# Ver2_1.net
KiCad netlist of a schematic drawn in EAGLE
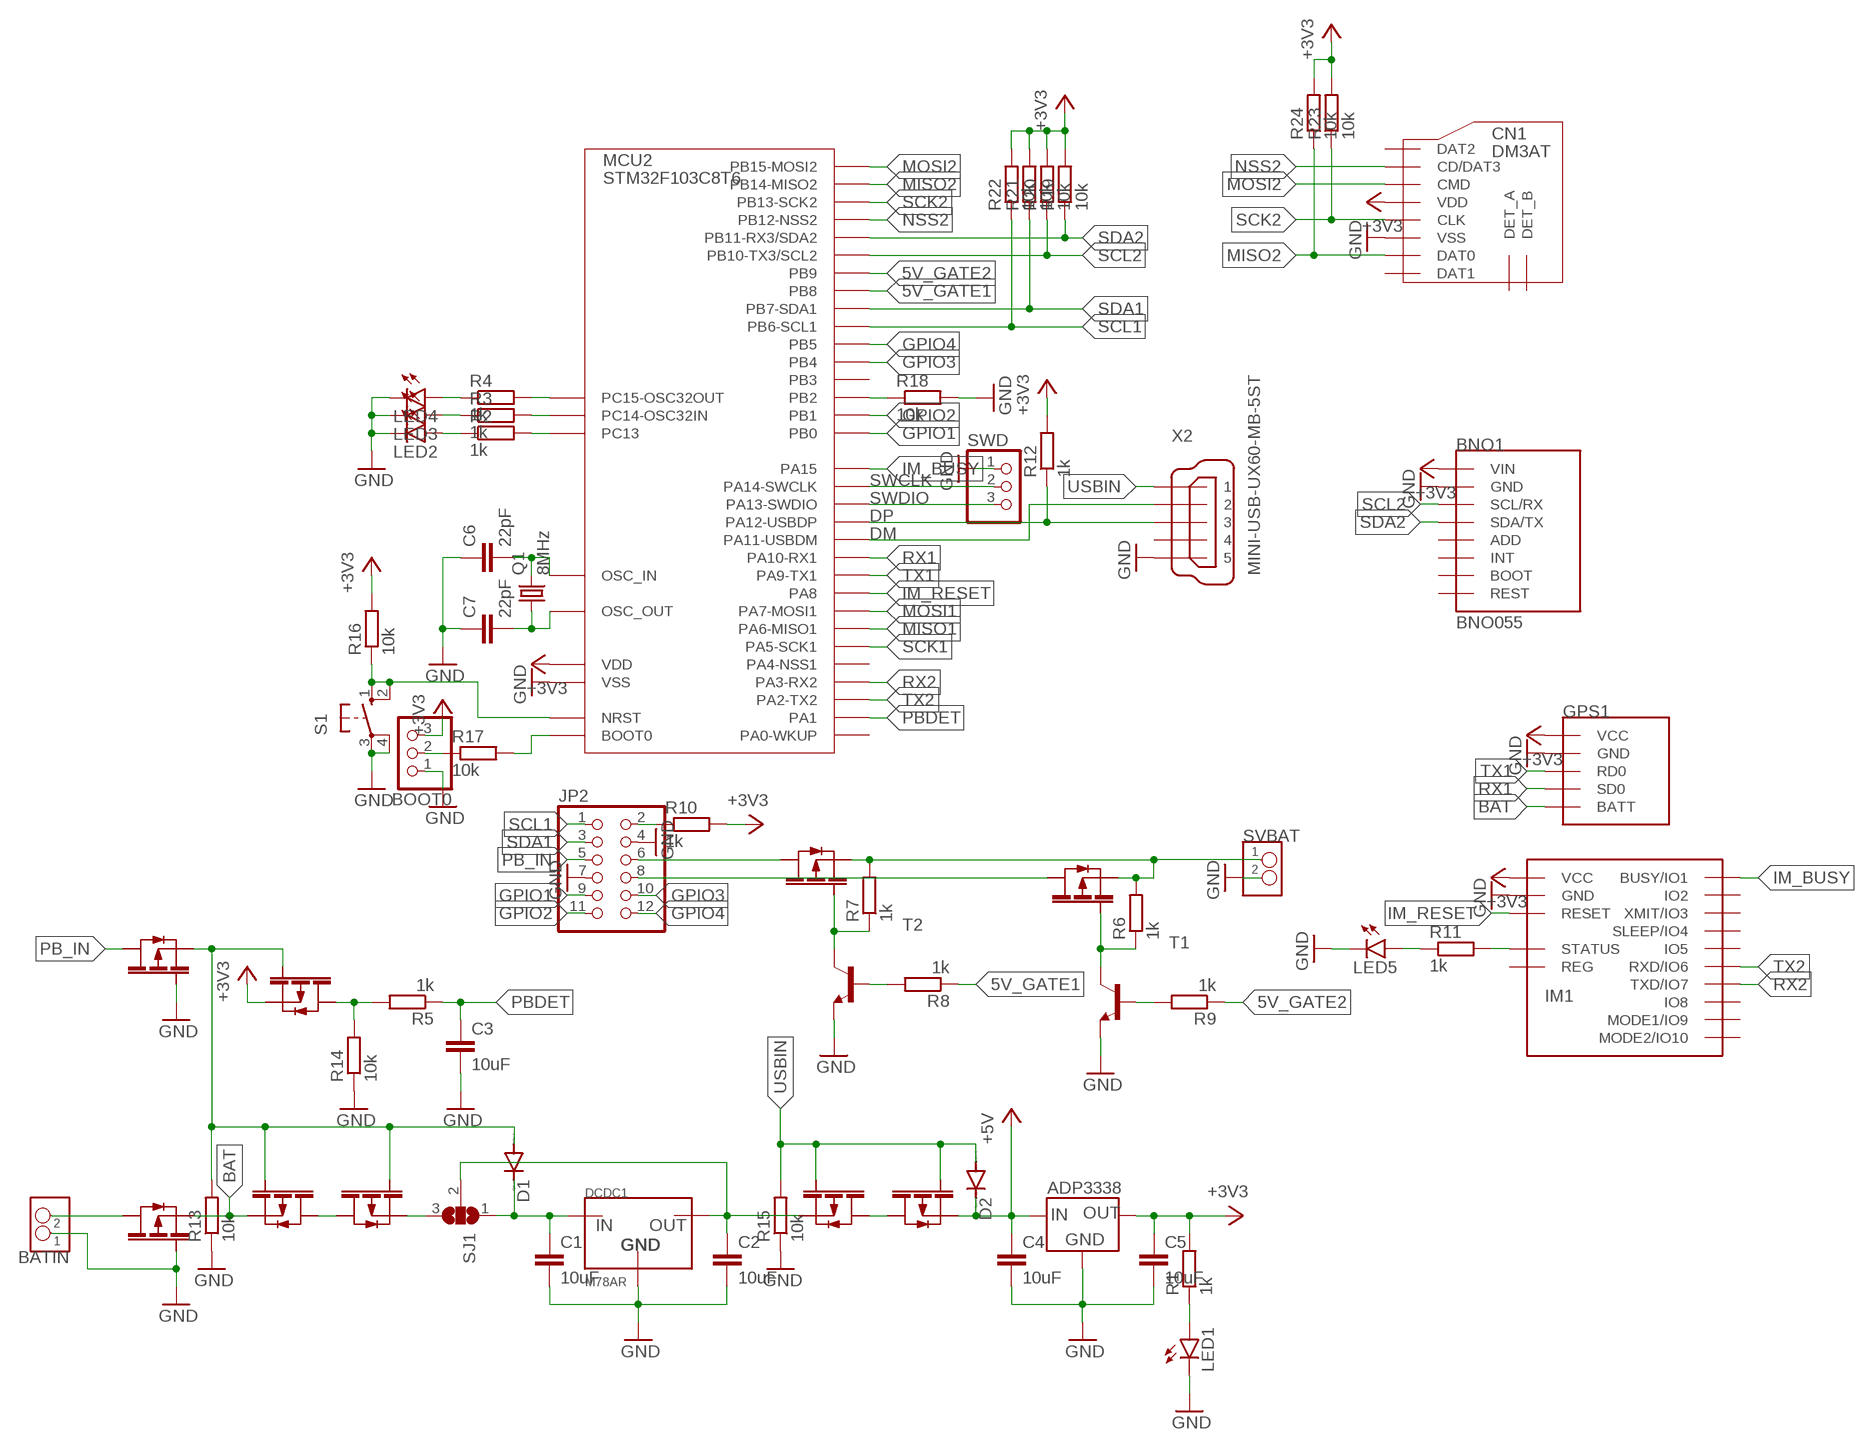
[diagram p0: schematic, sheet 1]

(export (version "E")
  (design (tool "Eeschema 10.0.6"))
  (components
    (comp (ref "BATIN")
      (value "S2B-XH-A")
      (footprint "eagle-import:S2B-XH-A")
      (libsource (lib "eagle-import") (part "S2B-XH-A"))
    )
    (comp (ref "BNO1")
      (value "BNO055")
      (footprint "eagle-import:BNO055")
      (libsource (lib "eagle-import") (part "BNO055"))
    )
    (comp (ref "BOOT0")
      (value "PINHD-1X3")
      (footprint "eagle-import:1X03")
      (libsource (lib "eagle-import") (part "PINHD-1X3"))
    )
    (comp (ref "C1")
      (value "10uF")
      (footprint "eagle-import:C2012")
      (libsource (lib "eagle-import") (part "C-EUC2012"))
    )
    (comp (ref "C2")
      (value "10uF")
      (footprint "eagle-import:C2012")
      (libsource (lib "eagle-import") (part "C-EUC2012"))
    )
    (comp (ref "C3")
      (value "10uF")
      (footprint "eagle-import:C2012")
      (libsource (lib "eagle-import") (part "C-EUC2012"))
    )
    (comp (ref "C4")
      (value "10uF")
      (footprint "eagle-import:C2012")
      (libsource (lib "eagle-import") (part "C-EUC2012"))
    )
    (comp (ref "C5")
      (value "10uF")
      (footprint "eagle-import:C2012")
      (libsource (lib "eagle-import") (part "C-EUC2012"))
    )
    (comp (ref "C6")
      (value "22pF")
      (footprint "eagle-import:C2012")
      (libsource (lib "eagle-import") (part "C-EUC2012"))
    )
    (comp (ref "C7")
      (value "22pF")
      (footprint "eagle-import:C2012")
      (libsource (lib "eagle-import") (part "C-EUC2012"))
    )
    (comp (ref "CN1")
      (value "DM3AT")
      (footprint "eagle-import:DM3AT")
      (libsource (lib "eagle-import") (part "DM3AT"))
    )
    (comp (ref "D1")
      (value "DIODE-SOD123")
      (footprint "eagle-import:SOD123")
      (libsource (lib "eagle-import") (part "DIODE-SOD123"))
    )
    (comp (ref "D2")
      (value "DIODE-SOD123")
      (footprint "eagle-import:SOD123")
      (libsource (lib "eagle-import") (part "DIODE-SOD123"))
    )
    (comp (ref "DCDC1")
      (value "M78AR")
      (footprint "eagle-import:M78AR")
      (libsource (lib "eagle-import") (part "M78AR"))
    )
    (comp (ref "FET1")
      (value "PCH")
      (footprint "eagle-import:SOT-23")
      (libsource (lib "eagle-import") (part "PCH"))
    )
    (comp (ref "FET2")
      (value "PCH")
      (footprint "eagle-import:SOT-23")
      (libsource (lib "eagle-import") (part "PCH"))
    )
    (comp (ref "FET3")
      (value "PCH")
      (footprint "eagle-import:SOT-23")
      (libsource (lib "eagle-import") (part "PCH"))
    )
    (comp (ref "FET4")
      (value "PCH")
      (footprint "eagle-import:SOT-23")
      (libsource (lib "eagle-import") (part "PCH"))
    )
    (comp (ref "FET5")
      (value "PCH")
      (footprint "eagle-import:SOT-23")
      (libsource (lib "eagle-import") (part "PCH"))
    )
    (comp (ref "FET6")
      (value "PCH")
      (footprint "eagle-import:SOT-23")
      (libsource (lib "eagle-import") (part "PCH"))
    )
    (comp (ref "FET7")
      (value "PCH")
      (footprint "eagle-import:SOT-23")
      (libsource (lib "eagle-import") (part "PCH"))
    )
    (comp (ref "FET8")
      (value "PCH")
      (footprint "eagle-import:SOT-23")
      (libsource (lib "eagle-import") (part "PCH"))
    )
    (comp (ref "FET9")
      (value "PCH")
      (footprint "eagle-import:SOT-23")
      (libsource (lib "eagle-import") (part "PCH"))
    )
    (comp (ref "GPS1")
      (value "GPS-54D")
      (footprint "eagle-import:GPS-54D")
      (libsource (lib "eagle-import") (part "GPS-54D"))
    )
    (comp (ref "IC1")
      (value "ADP3338-3.3")
      (footprint "eagle-import:SOT-223")
      (libsource (lib "eagle-import") (part "ADP3338-3.3"))
    )
    (comp (ref "IM1")
      (value "IM920C")
      (footprint "eagle-import:IM920C")
      (libsource (lib "eagle-import") (part "IM920C"))
    )
    (comp (ref "JP2")
      (value "PINHD-2X6")
      (footprint "eagle-import:2X06")
      (libsource (lib "eagle-import") (part "PINHD-2X6"))
    )
    (comp (ref "LED1")
      (value "LEDSMT1206")
      (footprint "eagle-import:1206")
      (libsource (lib "eagle-import") (part "LEDSMT1206"))
    )
    (comp (ref "LED2")
      (value "LEDSMT1206")
      (footprint "eagle-import:1206")
      (libsource (lib "eagle-import") (part "LEDSMT1206"))
    )
    (comp (ref "LED3")
      (value "LEDSMT1206")
      (footprint "eagle-import:1206")
      (libsource (lib "eagle-import") (part "LEDSMT1206"))
    )
    (comp (ref "LED4")
      (value "LEDSMT1206")
      (footprint "eagle-import:1206")
      (libsource (lib "eagle-import") (part "LEDSMT1206"))
    )
    (comp (ref "LED5")
      (value "LEDSMT1206")
      (footprint "eagle-import:1206")
      (libsource (lib "eagle-import") (part "LEDSMT1206"))
    )
    (comp (ref "MCU2")
      (value "STM32F103C8T6")
      (footprint "eagle-import:LQFP48")
      (libsource (lib "eagle-import") (part "STM32F103C8T6"))
    )
    (comp (ref "Q1")
      (value "8MHz")
      (footprint "eagle-import:HC49_S")
      (libsource (lib "eagle-import") (part "CRYSTALHC49S"))
    )
    (comp (ref "R1")
      (value "1k")
      (footprint "eagle-import:R2012")
      (libsource (lib "eagle-import") (part "R-EU_R2012"))
    )
    (comp (ref "R2")
      (value "1k")
      (footprint "eagle-import:R2012")
      (libsource (lib "eagle-import") (part "R-EU_R2012"))
    )
    (comp (ref "R3")
      (value "1k")
      (footprint "eagle-import:R2012")
      (libsource (lib "eagle-import") (part "R-EU_R2012"))
    )
    (comp (ref "R4")
      (value "1k")
      (footprint "eagle-import:R2012")
      (libsource (lib "eagle-import") (part "R-EU_R2012"))
    )
    (comp (ref "R5")
      (value "1k")
      (footprint "eagle-import:R2012")
      (libsource (lib "eagle-import") (part "R-EU_R2012"))
    )
    (comp (ref "R6")
      (value "1k")
      (footprint "eagle-import:R2012")
      (libsource (lib "eagle-import") (part "R-EU_R2012"))
    )
    (comp (ref "R7")
      (value "1k")
      (footprint "eagle-import:R2012")
      (libsource (lib "eagle-import") (part "R-EU_R2012"))
    )
    (comp (ref "R8")
      (value "1k")
      (footprint "eagle-import:R2012")
      (libsource (lib "eagle-import") (part "R-EU_R2012"))
    )
    (comp (ref "R9")
      (value "1k")
      (footprint "eagle-import:R2012")
      (libsource (lib "eagle-import") (part "R-EU_R2012"))
    )
    (comp (ref "R10")
      (value "1k")
      (footprint "eagle-import:R2012")
      (libsource (lib "eagle-import") (part "R-EU_R2012"))
    )
    (comp (ref "R11")
      (value "1k")
      (footprint "eagle-import:R2012")
      (libsource (lib "eagle-import") (part "R-EU_R2012"))
    )
    (comp (ref "R12")
      (value "1k")
      (footprint "eagle-import:R2012")
      (libsource (lib "eagle-import") (part "R-EU_R2012"))
    )
    (comp (ref "R13")
      (value "10k")
      (footprint "eagle-import:R2012")
      (libsource (lib "eagle-import") (part "R-EU_R2012"))
    )
    (comp (ref "R14")
      (value "10k")
      (footprint "eagle-import:R2012")
      (libsource (lib "eagle-import") (part "R-EU_R2012"))
    )
    (comp (ref "R15")
      (value "10k")
      (footprint "eagle-import:R2012")
      (libsource (lib "eagle-import") (part "R-EU_R2012"))
    )
    (comp (ref "R16")
      (value "10k")
      (footprint "eagle-import:R2012")
      (libsource (lib "eagle-import") (part "R-EU_R2012"))
    )
    (comp (ref "R17")
      (value "10k")
      (footprint "eagle-import:R2012")
      (libsource (lib "eagle-import") (part "R-EU_R2012"))
    )
    (comp (ref "R18")
      (value "10k")
      (footprint "eagle-import:R2012")
      (libsource (lib "eagle-import") (part "R-EU_R2012"))
    )
    (comp (ref "R19")
      (value "10k")
      (footprint "eagle-import:R2012")
      (libsource (lib "eagle-import") (part "R-EU_R2012"))
    )
    (comp (ref "R20")
      (value "10k")
      (footprint "eagle-import:R2012")
      (libsource (lib "eagle-import") (part "R-EU_R2012"))
    )
    (comp (ref "R21")
      (value "10k")
      (footprint "eagle-import:R2012")
      (libsource (lib "eagle-import") (part "R-EU_R2012"))
    )
    (comp (ref "R22")
      (value "10k")
      (footprint "eagle-import:R2012")
      (libsource (lib "eagle-import") (part "R-EU_R2012"))
    )
    (comp (ref "R23")
      (value "10k")
      (footprint "eagle-import:R2012")
      (libsource (lib "eagle-import") (part "R-EU_R2012"))
    )
    (comp (ref "R24")
      (value "10k")
      (footprint "eagle-import:R2012")
      (libsource (lib "eagle-import") (part "R-EU_R2012"))
    )
    (comp (ref "S1")
      (value "10-XX")
      (footprint "eagle-import:B3F-10XX")
      (fields (field (name "MPN") "B3F-1000"))
      (libsource (lib "eagle-import") (part "10-XX"))
    )
    (comp (ref "SJ1")
      (value "SJ2W")
      (footprint "eagle-import:SJ_2")
      (libsource (lib "eagle-import") (part "SJ2W"))
    )
    (comp (ref "SVBAT")
      (value "S2B-XH-A")
      (footprint "eagle-import:S2B-XH-A")
      (libsource (lib "eagle-import") (part "S2B-XH-A"))
    )
    (comp (ref "SWD")
      (value "PINHD-1X3")
      (footprint "eagle-import:1X03")
      (libsource (lib "eagle-import") (part "PINHD-1X3"))
    )
    (comp (ref "T1")
      (value "-NPN-SOT23-EBC")
      (footprint "eagle-import:SOT23-EBC")
      (libsource (lib "eagle-import") (part "-NPN-SOT23-EBC"))
    )
    (comp (ref "T2")
      (value "-NPN-SOT23-EBC")
      (footprint "eagle-import:SOT23-EBC")
      (libsource (lib "eagle-import") (part "-NPN-SOT23-EBC"))
    )
    (comp (ref "X2")
      (value "MINI-USB-UX60-MB-5ST")
      (footprint "eagle-import:UX60-MB-5ST")
      (libsource (lib "eagle-import") (part "MINI-USB-UX60-MB-5ST"))
    )
  )
  (nets
    (net (code "1") (name "+3V3") (class "Default")
      (node (ref "BNO1") (pin "P1") (pinfunction "VIN_P1") (pintype "bidirectional"))
      (node (ref "BOOT0") (pin "3") (pinfunction "3_3") (pintype "passive"))
      (node (ref "C5") (pin "1") (pinfunction "1_1") (pintype "passive"))
      (node (ref "CN1") (pin "VDD") (pinfunction "VDD_VDD") (pintype "bidirectional"))
      (node (ref "FET5") (pin "P$2") (pinfunction "P$2_P$2") (pintype "bidirectional"))
      (node (ref "GPS1") (pin "VCC") (pinfunction "VCC_VCC") (pintype "bidirectional"))
      (node (ref "IC1") (pin "1") (pinfunction "OUT_1") (pintype "output"))
      (node (ref "IC1") (pin "2") (pinfunction "OUT_2") (pintype "output"))
      (node (ref "IM1") (pin "$P17") (pinfunction "VCC_$P17") (pintype "bidirectional"))
      (node (ref "MCU2") (pin "1") (pinfunction "VDD_1") (pintype "bidirectional"))
      (node (ref "MCU2") (pin "24") (pinfunction "VDD_24") (pintype "bidirectional"))
      (node (ref "MCU2") (pin "36") (pinfunction "VDD_36") (pintype "bidirectional"))
      (node (ref "MCU2") (pin "48") (pinfunction "VDD_48") (pintype "bidirectional"))
      (node (ref "MCU2") (pin "9") (pinfunction "VDD_9") (pintype "bidirectional"))
      (node (ref "R1") (pin "2") (pinfunction "2_2") (pintype "passive"))
      (node (ref "R10") (pin "2") (pinfunction "2_2") (pintype "passive"))
      (node (ref "R12") (pin "2") (pinfunction "2_2") (pintype "passive"))
      (node (ref "R16") (pin "2") (pinfunction "2_2") (pintype "passive"))
      (node (ref "R19") (pin "2") (pinfunction "2_2") (pintype "passive"))
      (node (ref "R20") (pin "2") (pinfunction "2_2") (pintype "passive"))
      (node (ref "R21") (pin "2") (pinfunction "2_2") (pintype "passive"))
      (node (ref "R22") (pin "2") (pinfunction "2_2") (pintype "passive"))
      (node (ref "R23") (pin "2") (pinfunction "2_2") (pintype "passive"))
      (node (ref "R24") (pin "2") (pinfunction "2_2") (pintype "passive"))
    )
    (net (code "2") (name "+5V") (class "Default")
      (node (ref "C4") (pin "1") (pinfunction "1_1") (pintype "passive"))
      (node (ref "D2") (pin "C") (pinfunction "C_C") (pintype "passive"))
      (node (ref "FET7") (pin "P$2") (pinfunction "P$2_P$2") (pintype "bidirectional"))
      (node (ref "IC1") (pin "3") (pinfunction "IN_3") (pintype "input"))
    )
    (net (code "3") (name "/DM") (class "Default")
      (node (ref "MCU2") (pin "32") (pinfunction "PA11-USBDM_32") (pintype "bidirectional"))
      (node (ref "X2") (pin "2") (pinfunction "2_2") (pintype "input"))
    )
    (net (code "4") (name "/DP") (class "Default")
      (node (ref "MCU2") (pin "33") (pinfunction "PA12-USBDP_33") (pintype "bidirectional"))
      (node (ref "R12") (pin "1") (pinfunction "1_1") (pintype "passive"))
      (node (ref "X2") (pin "3") (pinfunction "3_3") (pintype "input"))
    )
    (net (code "5") (name "/SWCLK") (class "Default")
      (node (ref "MCU2") (pin "37") (pinfunction "PA14-SWCLK_37") (pintype "bidirectional"))
      (node (ref "SWD") (pin "2") (pinfunction "2_2") (pintype "passive"))
    )
    (net (code "6") (name "/SWDIO") (class "Default")
      (node (ref "MCU2") (pin "34") (pinfunction "PA13-SWDIO_34") (pintype "bidirectional"))
      (node (ref "SWD") (pin "3") (pinfunction "3_3") (pintype "passive"))
    )
    (net (code "7") (name "5V_GATE1") (class "Default")
      (node (ref "MCU2") (pin "45") (pinfunction "PB8_45") (pintype "bidirectional"))
      (node (ref "R8") (pin "1") (pinfunction "1_1") (pintype "passive"))
    )
    (net (code "8") (name "5V_GATE2") (class "Default")
      (node (ref "MCU2") (pin "46") (pinfunction "PB9_46") (pintype "bidirectional"))
      (node (ref "R9") (pin "1") (pinfunction "1_1") (pintype "passive"))
    )
    (net (code "9") (name "BAT") (class "Default")
      (node (ref "FET2") (pin "P$2") (pinfunction "P$2_P$2") (pintype "bidirectional"))
      (node (ref "FET3") (pin "P$2") (pinfunction "P$2_P$2") (pintype "bidirectional"))
      (node (ref "GPS1") (pin "BATT") (pinfunction "BATT_BATT") (pintype "bidirectional"))
    )
    (net (code "10") (name "GND") (class "Default")
      (node (ref "BATIN") (pin "P$1") (pinfunction "1_P$1") (pintype "bidirectional"))
      (node (ref "BNO1") (pin "P2") (pinfunction "GND_P2") (pintype "bidirectional"))
      (node (ref "BOOT0") (pin "1") (pinfunction "1_1") (pintype "passive"))
      (node (ref "C1") (pin "2") (pinfunction "2_2") (pintype "passive"))
      (node (ref "C2") (pin "2") (pinfunction "2_2") (pintype "passive"))
      (node (ref "C3") (pin "2") (pinfunction "2_2") (pintype "passive"))
      (node (ref "C4") (pin "2") (pinfunction "2_2") (pintype "passive"))
      (node (ref "C5") (pin "2") (pinfunction "2_2") (pintype "passive"))
      (node (ref "C6") (pin "1") (pinfunction "1_1") (pintype "passive"))
      (node (ref "C7") (pin "1") (pinfunction "1_1") (pintype "passive"))
      (node (ref "CN1") (pin "VSS") (pinfunction "VSS_VSS") (pintype "bidirectional"))
      (node (ref "DCDC1") (pin "P2") (pinfunction "GND_P2") (pintype "bidirectional"))
      (node (ref "FET1") (pin "P$1") (pinfunction "P$1_P$1") (pintype "bidirectional"))
      (node (ref "FET2") (pin "P$1") (pinfunction "P$1_P$1") (pintype "bidirectional"))
      (node (ref "GPS1") (pin "GND") (pinfunction "GND_GND") (pintype "bidirectional"))
      (node (ref "IC1") (pin "4") (pinfunction "GND_4") (pintype "bidirectional"))
      (node (ref "IM1") (pin "$P18") (pinfunction "GND_$P18") (pintype "bidirectional"))
      (node (ref "JP2") (pin "4") (pinfunction "4_4") (pintype "passive"))
      (node (ref "JP2") (pin "7") (pinfunction "7_7") (pintype "passive"))
      (node (ref "LED1") (pin "C") (pinfunction "C_C") (pintype "passive"))
      (node (ref "LED2") (pin "C") (pinfunction "C_C") (pintype "passive"))
      (node (ref "LED3") (pin "C") (pinfunction "C_C") (pintype "passive"))
      (node (ref "LED4") (pin "C") (pinfunction "C_C") (pintype "passive"))
      (node (ref "LED5") (pin "C") (pinfunction "C_C") (pintype "passive"))
      (node (ref "MCU2") (pin "23") (pinfunction "VSS_23") (pintype "bidirectional"))
      (node (ref "MCU2") (pin "35") (pinfunction "VSS_35") (pintype "bidirectional"))
      (node (ref "MCU2") (pin "47") (pinfunction "VSS_47") (pintype "bidirectional"))
      (node (ref "MCU2") (pin "8") (pinfunction "VSS_8") (pintype "bidirectional"))
      (node (ref "R13") (pin "1") (pinfunction "1_1") (pintype "passive"))
      (node (ref "R14") (pin "1") (pinfunction "1_1") (pintype "passive"))
      (node (ref "R15") (pin "1") (pinfunction "1_1") (pintype "passive"))
      (node (ref "R18") (pin "2") (pinfunction "2_2") (pintype "passive"))
      (node (ref "S1") (pin "3") (pinfunction "P_3") (pintype "passive"))
      (node (ref "S1") (pin "4") (pinfunction "P1_4") (pintype "passive"))
      (node (ref "SVBAT") (pin "P$2") (pinfunction "2_P$2") (pintype "bidirectional"))
      (node (ref "SWD") (pin "1") (pinfunction "1_1") (pintype "passive"))
      (node (ref "T1") (pin "E") (pinfunction "E_E") (pintype "passive"))
      (node (ref "T2") (pin "E") (pinfunction "E_E") (pintype "passive"))
      (node (ref "X2") (pin "5") (pinfunction "5_5") (pintype "input"))
    )
    (net (code "11") (name "GPIO1") (class "Default")
      (node (ref "JP2") (pin "9") (pinfunction "9_9") (pintype "passive"))
      (node (ref "MCU2") (pin "18") (pinfunction "PB0_18") (pintype "bidirectional"))
    )
    (net (code "12") (name "GPIO2") (class "Default")
      (node (ref "JP2") (pin "11") (pinfunction "11_11") (pintype "passive"))
      (node (ref "MCU2") (pin "19") (pinfunction "PB1_19") (pintype "bidirectional"))
    )
    (net (code "13") (name "GPIO3") (class "Default")
      (node (ref "JP2") (pin "10") (pinfunction "10_10") (pintype "passive"))
      (node (ref "MCU2") (pin "40") (pinfunction "PB4_40") (pintype "bidirectional"))
    )
    (net (code "14") (name "GPIO4") (class "Default")
      (node (ref "JP2") (pin "12") (pinfunction "12_12") (pintype "passive"))
      (node (ref "MCU2") (pin "41") (pinfunction "PB5_41") (pintype "bidirectional"))
    )
    (net (code "15") (name "IM_BUSY") (class "Default")
      (node (ref "IM1") (pin "$P1") (pinfunction "BUSY/IO1_$P1") (pintype "bidirectional"))
      (node (ref "MCU2") (pin "38") (pinfunction "PA15_38") (pintype "bidirectional"))
    )
    (net (code "16") (name "IM_RESET") (class "Default")
      (node (ref "IM1") (pin "$P19") (pinfunction "RESET_$P19") (pintype "bidirectional"))
      (node (ref "MCU2") (pin "29") (pinfunction "PA8_29") (pintype "bidirectional"))
    )
    (net (code "17") (name "MISO1") (class "Default")
      (node (ref "MCU2") (pin "16") (pinfunction "PA6-MISO1_16") (pintype "bidirectional"))
    )
    (net (code "18") (name "MISO2") (class "Default")
      (node (ref "CN1") (pin "DAT0") (pinfunction "DAT0_DAT0") (pintype "bidirectional"))
      (node (ref "MCU2") (pin "27") (pinfunction "PB14-MISO2_27") (pintype "bidirectional"))
      (node (ref "R24") (pin "1") (pinfunction "1_1") (pintype "passive"))
    )
    (net (code "19") (name "MOSI1") (class "Default")
      (node (ref "MCU2") (pin "17") (pinfunction "PA7-MOSI1_17") (pintype "bidirectional"))
    )
    (net (code "20") (name "MOSI2") (class "Default")
      (node (ref "CN1") (pin "CMD") (pinfunction "CMD_CMD") (pintype "bidirectional"))
      (node (ref "MCU2") (pin "28") (pinfunction "PB15-MOSI2_28") (pintype "bidirectional"))
    )
    (net (code "21") (name "NSS2") (class "Default")
      (node (ref "CN1") (pin "CD/DAT3") (pinfunction "CD/DAT3_CD/DAT3") (pintype "bidirectional"))
      (node (ref "MCU2") (pin "25") (pinfunction "PB12-NSS2_25") (pintype "bidirectional"))
    )
    (net (code "22") (name "Net-(BATIN-2)") (class "Default")
      (node (ref "BATIN") (pin "P$2") (pinfunction "2_P$2") (pintype "bidirectional"))
      (node (ref "FET2") (pin "P$3") (pinfunction "P$3_P$3") (pintype "bidirectional"))
    )
    (net (code "23") (name "Net-(BOOT0-Pad2)") (class "Default")
      (node (ref "BOOT0") (pin "2") (pinfunction "2_2") (pintype "passive"))
      (node (ref "R17") (pin "1") (pinfunction "1_1") (pintype "passive"))
    )
    (net (code "24") (name "Net-(D1-PadA)") (class "Default")
      (node (ref "D1") (pin "A") (pinfunction "A_A") (pintype "passive"))
      (node (ref "FET1") (pin "P$2") (pinfunction "P$2_P$2") (pintype "bidirectional"))
      (node (ref "FET3") (pin "P$1") (pinfunction "P$1_P$1") (pintype "bidirectional"))
      (node (ref "FET4") (pin "P$1") (pinfunction "P$1_P$1") (pintype "bidirectional"))
      (node (ref "FET5") (pin "P$1") (pinfunction "P$1_P$1") (pintype "bidirectional"))
      (node (ref "R13") (pin "2") (pinfunction "2_2") (pintype "passive"))
    )
    (net (code "25") (name "Net-(DCDC1-IN)") (class "Default")
      (node (ref "C1") (pin "1") (pinfunction "1_1") (pintype "passive"))
      (node (ref "D1") (pin "C") (pinfunction "C_C") (pintype "passive"))
      (node (ref "DCDC1") (pin "P3") (pinfunction "IN_P3") (pintype "bidirectional"))
      (node (ref "SJ1") (pin "1") (pinfunction "1_1") (pintype "passive"))
    )
    (net (code "26") (name "Net-(DCDC1-OUT)") (class "Default")
      (node (ref "C2") (pin "1") (pinfunction "1_1") (pintype "passive"))
      (node (ref "DCDC1") (pin "P1") (pinfunction "OUT_P1") (pintype "bidirectional"))
      (node (ref "FET6") (pin "P$2") (pinfunction "P$2_P$2") (pintype "bidirectional"))
      (node (ref "SJ1") (pin "2") (pinfunction "2_2") (pintype "passive"))
    )
    (net (code "27") (name "Net-(FET3-PadP$3)") (class "Default")
      (node (ref "FET3") (pin "P$3") (pinfunction "P$3_P$3") (pintype "bidirectional"))
      (node (ref "FET4") (pin "P$3") (pinfunction "P$3_P$3") (pintype "bidirectional"))
    )
    (net (code "28") (name "Net-(FET4-PadP$2)") (class "Default")
      (node (ref "FET4") (pin "P$2") (pinfunction "P$2_P$2") (pintype "bidirectional"))
      (node (ref "SJ1") (pin "3") (pinfunction "3_3") (pintype "passive"))
    )
    (net (code "29") (name "Net-(FET5-PadP$3)") (class "Default")
      (node (ref "FET5") (pin "P$3") (pinfunction "P$3_P$3") (pintype "bidirectional"))
      (node (ref "R14") (pin "2") (pinfunction "2_2") (pintype "passive"))
      (node (ref "R5") (pin "2") (pinfunction "2_2") (pintype "passive"))
    )
    (net (code "30") (name "Net-(FET6-PadP$3)") (class "Default")
      (node (ref "FET6") (pin "P$3") (pinfunction "P$3_P$3") (pintype "bidirectional"))
      (node (ref "FET7") (pin "P$3") (pinfunction "P$3_P$3") (pintype "bidirectional"))
    )
    (net (code "31") (name "Net-(FET8-PadP$1)") (class "Default")
      (node (ref "FET8") (pin "P$1") (pinfunction "P$1_P$1") (pintype "bidirectional"))
      (node (ref "R7") (pin "1") (pinfunction "1_1") (pintype "passive"))
      (node (ref "T2") (pin "C") (pinfunction "C_C") (pintype "passive"))
    )
    (net (code "32") (name "Net-(FET8-PadP$3)") (class "Default")
      (node (ref "FET8") (pin "P$3") (pinfunction "P$3_P$3") (pintype "bidirectional"))
      (node (ref "JP2") (pin "6") (pinfunction "6_6") (pintype "passive"))
    )
    (net (code "33") (name "Net-(FET9-PadP$1)") (class "Default")
      (node (ref "FET9") (pin "P$1") (pinfunction "P$1_P$1") (pintype "bidirectional"))
      (node (ref "R6") (pin "1") (pinfunction "1_1") (pintype "passive"))
      (node (ref "T1") (pin "C") (pinfunction "C_C") (pintype "passive"))
    )
    (net (code "34") (name "Net-(FET9-PadP$3)") (class "Default")
      (node (ref "FET9") (pin "P$3") (pinfunction "P$3_P$3") (pintype "bidirectional"))
      (node (ref "JP2") (pin "8") (pinfunction "8_8") (pintype "passive"))
    )
    (net (code "35") (name "Net-(IM1-STATUS)") (class "Default")
      (node (ref "IM1") (pin "$P15") (pinfunction "STATUS_$P15") (pintype "bidirectional"))
      (node (ref "R11") (pin "2") (pinfunction "2_2") (pintype "passive"))
    )
    (net (code "36") (name "Net-(JP2-Pad2)") (class "Default")
      (node (ref "JP2") (pin "2") (pinfunction "2_2") (pintype "passive"))
      (node (ref "R10") (pin "1") (pinfunction "1_1") (pintype "passive"))
    )
    (net (code "37") (name "Net-(LED1-PadA)") (class "Default")
      (node (ref "LED1") (pin "A") (pinfunction "A_A") (pintype "passive"))
      (node (ref "R1") (pin "1") (pinfunction "1_1") (pintype "passive"))
    )
    (net (code "38") (name "Net-(LED2-PadA)") (class "Default")
      (node (ref "LED2") (pin "A") (pinfunction "A_A") (pintype "passive"))
      (node (ref "R2") (pin "1") (pinfunction "1_1") (pintype "passive"))
    )
    (net (code "39") (name "Net-(LED3-PadA)") (class "Default")
      (node (ref "LED3") (pin "A") (pinfunction "A_A") (pintype "passive"))
      (node (ref "R3") (pin "1") (pinfunction "1_1") (pintype "passive"))
    )
    (net (code "40") (name "Net-(LED4-PadA)") (class "Default")
      (node (ref "LED4") (pin "A") (pinfunction "A_A") (pintype "passive"))
      (node (ref "R4") (pin "1") (pinfunction "1_1") (pintype "passive"))
    )
    (net (code "41") (name "Net-(LED5-PadA)") (class "Default")
      (node (ref "LED5") (pin "A") (pinfunction "A_A") (pintype "passive"))
      (node (ref "R11") (pin "1") (pinfunction "1_1") (pintype "passive"))
    )
    (net (code "42") (name "Net-(MCU2-BOOT0)") (class "Default")
      (node (ref "MCU2") (pin "44") (pinfunction "BOOT0_44") (pintype "bidirectional"))
      (node (ref "R17") (pin "2") (pinfunction "2_2") (pintype "passive"))
    )
    (net (code "43") (name "Net-(MCU2-NRST)") (class "Default")
      (node (ref "MCU2") (pin "7") (pinfunction "NRST_7") (pintype "bidirectional"))
      (node (ref "R16") (pin "1") (pinfunction "1_1") (pintype "passive"))
      (node (ref "S1") (pin "1") (pinfunction "S_1") (pintype "passive"))
      (node (ref "S1") (pin "2") (pinfunction "S1_2") (pintype "passive"))
    )
    (net (code "44") (name "Net-(MCU2-OSC_IN)") (class "Default")
      (node (ref "C6") (pin "2") (pinfunction "2_2") (pintype "passive"))
      (node (ref "MCU2") (pin "5") (pinfunction "OSC_IN_5") (pintype "bidirectional"))
      (node (ref "Q1") (pin "2") (pinfunction "2_2") (pintype "passive"))
    )
    (net (code "45") (name "Net-(MCU2-OSC_OUT)") (class "Default")
      (node (ref "C7") (pin "2") (pinfunction "2_2") (pintype "passive"))
      (node (ref "MCU2") (pin "6") (pinfunction "OSC_OUT_6") (pintype "bidirectional"))
      (node (ref "Q1") (pin "1") (pinfunction "1_1") (pintype "passive"))
    )
    (net (code "46") (name "Net-(MCU2-PB2)") (class "Default")
      (node (ref "MCU2") (pin "20") (pinfunction "PB2_20") (pintype "bidirectional"))
      (node (ref "R18") (pin "1") (pinfunction "1_1") (pintype "passive"))
    )
    (net (code "47") (name "Net-(MCU2-PC13)") (class "Default")
      (node (ref "MCU2") (pin "2") (pinfunction "PC13_2") (pintype "bidirectional"))
      (node (ref "R2") (pin "2") (pinfunction "2_2") (pintype "passive"))
    )
    (net (code "48") (name "Net-(MCU2-PC14-OSC32IN)") (class "Default")
      (node (ref "MCU2") (pin "3") (pinfunction "PC14-OSC32IN_3") (pintype "bidirectional"))
      (node (ref "R3") (pin "2") (pinfunction "2_2") (pintype "passive"))
    )
    (net (code "49") (name "Net-(MCU2-PC15-OSC32OUT)") (class "Default")
      (node (ref "MCU2") (pin "4") (pinfunction "PC15-OSC32OUT_4") (pintype "bidirectional"))
      (node (ref "R4") (pin "2") (pinfunction "2_2") (pintype "passive"))
    )
    (net (code "50") (name "Net-(R8-Pad2)") (class "Default")
      (node (ref "R8") (pin "2") (pinfunction "2_2") (pintype "passive"))
      (node (ref "T2") (pin "B") (pinfunction "B_B") (pintype "passive"))
    )
    (net (code "51") (name "Net-(R9-Pad2)") (class "Default")
      (node (ref "R9") (pin "2") (pinfunction "2_2") (pintype "passive"))
      (node (ref "T1") (pin "B") (pinfunction "B_B") (pintype "passive"))
    )
    (net (code "52") (name "Net-(SVBAT-1)") (class "Default")
      (node (ref "FET8") (pin "P$2") (pinfunction "P$2_P$2") (pintype "bidirectional"))
      (node (ref "FET9") (pin "P$2") (pinfunction "P$2_P$2") (pintype "bidirectional"))
      (node (ref "R6") (pin "2") (pinfunction "2_2") (pintype "passive"))
      (node (ref "R7") (pin "2") (pinfunction "2_2") (pintype "passive"))
      (node (ref "SVBAT") (pin "P$1") (pinfunction "1_P$1") (pintype "bidirectional"))
    )
    (net (code "53") (name "PBDET") (class "Default")
      (node (ref "C3") (pin "1") (pinfunction "1_1") (pintype "passive"))
      (node (ref "MCU2") (pin "11") (pinfunction "PA1_11") (pintype "bidirectional"))
      (node (ref "R5") (pin "1") (pinfunction "1_1") (pintype "passive"))
    )
    (net (code "54") (name "PB_IN") (class "Default")
      (node (ref "FET1") (pin "P$3") (pinfunction "P$3_P$3") (pintype "bidirectional"))
      (node (ref "JP2") (pin "5") (pinfunction "5_5") (pintype "passive"))
    )
    (net (code "55") (name "RX1") (class "Default")
      (node (ref "GPS1") (pin "SD0") (pinfunction "SD0_SD0") (pintype "bidirectional"))
      (node (ref "MCU2") (pin "31") (pinfunction "PA10-RX1_31") (pintype "bidirectional"))
    )
    (net (code "56") (name "RX2") (class "Default")
      (node (ref "IM1") (pin "$P7") (pinfunction "TXD/IO7_$P7") (pintype "bidirectional"))
      (node (ref "MCU2") (pin "13") (pinfunction "PA3-RX2_13") (pintype "bidirectional"))
    )
    (net (code "57") (name "SCK1") (class "Default")
      (node (ref "MCU2") (pin "15") (pinfunction "PA5-SCK1_15") (pintype "bidirectional"))
    )
    (net (code "58") (name "SCK2") (class "Default")
      (node (ref "CN1") (pin "CLK") (pinfunction "CLK_CLK") (pintype "bidirectional"))
      (node (ref "MCU2") (pin "26") (pinfunction "PB13-SCK2_26") (pintype "bidirectional"))
      (node (ref "R23") (pin "1") (pinfunction "1_1") (pintype "passive"))
    )
    (net (code "59") (name "SCL1") (class "Default")
      (node (ref "JP2") (pin "1") (pinfunction "1_1") (pintype "passive"))
      (node (ref "MCU2") (pin "42") (pinfunction "PB6-SCL1_42") (pintype "bidirectional"))
      (node (ref "R22") (pin "1") (pinfunction "1_1") (pintype "passive"))
    )
    (net (code "60") (name "SCL2") (class "Default")
      (node (ref "BNO1") (pin "P3") (pinfunction "SCL/RX_P3") (pintype "bidirectional"))
      (node (ref "MCU2") (pin "21") (pinfunction "PB10-TX3/SCL2_21") (pintype "bidirectional"))
      (node (ref "R20") (pin "1") (pinfunction "1_1") (pintype "passive"))
    )
    (net (code "61") (name "SDA1") (class "Default")
      (node (ref "JP2") (pin "3") (pinfunction "3_3") (pintype "passive"))
      (node (ref "MCU2") (pin "43") (pinfunction "PB7-SDA1_43") (pintype "bidirectional"))
      (node (ref "R21") (pin "1") (pinfunction "1_1") (pintype "passive"))
    )
    (net (code "62") (name "SDA2") (class "Default")
      (node (ref "BNO1") (pin "P4") (pinfunction "SDA/TX_P4") (pintype "bidirectional"))
      (node (ref "MCU2") (pin "22") (pinfunction "PB11-RX3/SDA2_22") (pintype "bidirectional"))
      (node (ref "R19") (pin "1") (pinfunction "1_1") (pintype "passive"))
    )
    (net (code "63") (name "TX1") (class "Default")
      (node (ref "GPS1") (pin "RD0") (pinfunction "RD0_RD0") (pintype "bidirectional"))
      (node (ref "MCU2") (pin "30") (pinfunction "PA9-TX1_30") (pintype "bidirectional"))
    )
    (net (code "64") (name "TX2") (class "Default")
      (node (ref "IM1") (pin "$P6") (pinfunction "RXD/IO6_$P6") (pintype "bidirectional"))
      (node (ref "MCU2") (pin "12") (pinfunction "PA2-TX2_12") (pintype "bidirectional"))
    )
    (net (code "65") (name "USBIN") (class "Default")
      (node (ref "D2") (pin "A") (pinfunction "A_A") (pintype "passive"))
      (node (ref "FET6") (pin "P$1") (pinfunction "P$1_P$1") (pintype "bidirectional"))
      (node (ref "FET7") (pin "P$1") (pinfunction "P$1_P$1") (pintype "bidirectional"))
      (node (ref "R15") (pin "2") (pinfunction "2_2") (pintype "passive"))
      (node (ref "X2") (pin "1") (pinfunction "1_1") (pintype "input"))
    )
    (net (code "66") (name "unconnected-(BNO1-ADD-PadP5)") (class "Default")
      (node (ref "BNO1") (pin "P5") (pinfunction "ADD_P5") (pintype "bidirectional"))
    )
    (net (code "67") (name "unconnected-(BNO1-BOOT-PadP7)") (class "Default")
      (node (ref "BNO1") (pin "P7") (pinfunction "BOOT_P7") (pintype "bidirectional"))
    )
    (net (code "68") (name "unconnected-(BNO1-INT-PadP6)") (class "Default")
      (node (ref "BNO1") (pin "P6") (pinfunction "INT_P6") (pintype "bidirectional"))
    )
    (net (code "69") (name "unconnected-(BNO1-REST-PadP8)") (class "Default")
      (node (ref "BNO1") (pin "P8") (pinfunction "REST_P8") (pintype "bidirectional"))
    )
    (net (code "70") (name "unconnected-(CN1-PadDAT1)") (class "Default")
      (node (ref "CN1") (pin "DAT1") (pinfunction "DAT1_DAT1") (pintype "bidirectional"))
    )
    (net (code "71") (name "unconnected-(CN1-PadDAT2)") (class "Default")
      (node (ref "CN1") (pin "DAT2") (pinfunction "DAT2_DAT2") (pintype "bidirectional"))
    )
    (net (code "72") (name "unconnected-(CN1-PadDET_A)") (class "Default")
      (node (ref "CN1") (pin "DET_A") (pinfunction "DET_A_DET_A") (pintype "bidirectional"))
    )
    (net (code "73") (name "unconnected-(CN1-PadDET_B)") (class "Default")
      (node (ref "CN1") (pin "DET_B") (pinfunction "DET_B_DET_B") (pintype "bidirectional"))
    )
    (net (code "74") (name "unconnected-(IM1-IO2-Pad$P2)") (class "Default")
      (node (ref "IM1") (pin "$P2") (pinfunction "IO2_$P2") (pintype "bidirectional"))
    )
    (net (code "75") (name "unconnected-(IM1-IO5-Pad$P5)") (class "Default")
      (node (ref "IM1") (pin "$P5") (pinfunction "IO5_$P5") (pintype "bidirectional"))
    )
    (net (code "76") (name "unconnected-(IM1-IO8-Pad$P8)") (class "Default")
      (node (ref "IM1") (pin "$P8") (pinfunction "IO8_$P8") (pintype "bidirectional"))
    )
    (net (code "77") (name "unconnected-(IM1-MODE1{slash}IO9-Pad$P9)") (class "Default")
      (node (ref "IM1") (pin "$P9") (pinfunction "MODE1/IO9_$P9") (pintype "bidirectional"))
    )
    (net (code "78") (name "unconnected-(IM1-MODE2{slash}IO10-Pad$P10)") (class "Default")
      (node (ref "IM1") (pin "$P10") (pinfunction "MODE2/IO10_$P10") (pintype "bidirectional"))
    )
    (net (code "79") (name "unconnected-(IM1-REG-Pad$P16)") (class "Default")
      (node (ref "IM1") (pin "$P16") (pinfunction "REG_$P16") (pintype "bidirectional"))
    )
    (net (code "80") (name "unconnected-(IM1-SLEEP{slash}IO4-Pad$P4)") (class "Default")
      (node (ref "IM1") (pin "$P4") (pinfunction "SLEEP/IO4_$P4") (pintype "bidirectional"))
    )
    (net (code "81") (name "unconnected-(IM1-XMIT{slash}IO3-Pad$P3)") (class "Default")
      (node (ref "IM1") (pin "$P3") (pinfunction "XMIT/IO3_$P3") (pintype "bidirectional"))
    )
    (net (code "82") (name "unconnected-(MCU2-PA0-WKUP-Pad10)") (class "Default")
      (node (ref "MCU2") (pin "10") (pinfunction "PA0-WKUP_10") (pintype "bidirectional"))
    )
    (net (code "83") (name "unconnected-(MCU2-PA4-NSS1-Pad14)") (class "Default")
      (node (ref "MCU2") (pin "14") (pinfunction "PA4-NSS1_14") (pintype "bidirectional"))
    )
    (net (code "84") (name "unconnected-(MCU2-PB3-Pad39)") (class "Default")
      (node (ref "MCU2") (pin "39") (pinfunction "PB3_39") (pintype "bidirectional"))
    )
    (net (code "85") (name "unconnected-(X2-Pad4)") (class "Default")
      (node (ref "X2") (pin "4") (pinfunction "4_4") (pintype "input"))
    )
  )
)
